# Euro5VDCDC.net
KiCad netlist of a schematic drawn in EAGLE
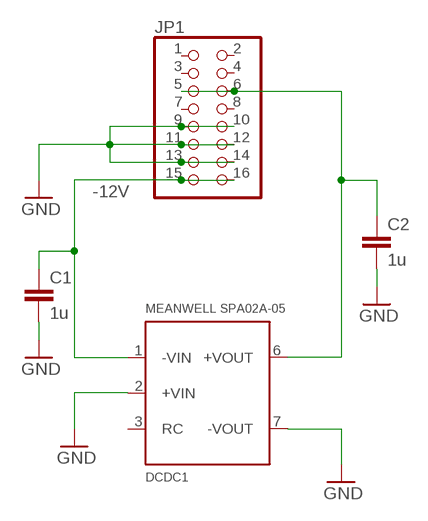
[diagram p0: schematic, sheet 1]

(export (version "E")
  (design (tool "Eeschema 10.0.6"))
  (components
    (comp (ref "C1")
      (value "1u")
      (footprint "eagle-import:C1206K")
      (libsource (lib "eagle-import") (part "C-EUC1206K"))
    )
    (comp (ref "C2")
      (value "1u")
      (footprint "eagle-import:C1206K")
      (libsource (lib "eagle-import") (part "C-EUC1206K"))
    )
    (comp (ref "DCDC1")
      (value "MEANWELL SPA02A-05")
      (footprint "eagle-import:MEANWELL_SPA02")
      (libsource (lib "eagle-import") (part "MEANWELL_SPA02"))
    )
    (comp (ref "JP1")
      (value "PINHD-2X8")
      (footprint "eagle-import:2X08")
      (libsource (lib "eagle-import") (part "PINHD-2X8"))
    )
  )
  (nets
    (net (code "1") (name "/-12V") (class "Default")
      (node (ref "C1") (pin "1") (pinfunction "1_1") (pintype "passive"))
      (node (ref "DCDC1") (pin "1") (pinfunction "-VIN_1") (pintype "bidirectional"))
      (node (ref "JP1") (pin "15") (pinfunction "15_15") (pintype "passive"))
      (node (ref "JP1") (pin "16") (pinfunction "16_16") (pintype "passive"))
    )
    (net (code "2") (name "GND") (class "Default")
      (node (ref "C1") (pin "2") (pinfunction "2_2") (pintype "passive"))
      (node (ref "C2") (pin "2") (pinfunction "2_2") (pintype "passive"))
      (node (ref "DCDC1") (pin "2") (pinfunction "+VIN_2") (pintype "bidirectional"))
      (node (ref "DCDC1") (pin "7") (pinfunction "-VOUT_7") (pintype "bidirectional"))
      (node (ref "JP1") (pin "10") (pinfunction "10_10") (pintype "passive"))
      (node (ref "JP1") (pin "11") (pinfunction "11_11") (pintype "passive"))
      (node (ref "JP1") (pin "12") (pinfunction "12_12") (pintype "passive"))
      (node (ref "JP1") (pin "13") (pinfunction "13_13") (pintype "passive"))
      (node (ref "JP1") (pin "14") (pinfunction "14_14") (pintype "passive"))
      (node (ref "JP1") (pin "9") (pinfunction "9_9") (pintype "passive"))
    )
    (net (code "3") (name "Net-(DCDC1-+VOUT)") (class "Default")
      (node (ref "C2") (pin "1") (pinfunction "1_1") (pintype "passive"))
      (node (ref "DCDC1") (pin "6") (pinfunction "+VOUT_6") (pintype "bidirectional"))
      (node (ref "JP1") (pin "5") (pinfunction "5_5") (pintype "passive"))
      (node (ref "JP1") (pin "6") (pinfunction "6_6") (pintype "passive"))
    )
    (net (code "4") (name "unconnected-(DCDC1-RC-Pad3)") (class "Default")
      (node (ref "DCDC1") (pin "3") (pinfunction "RC_3") (pintype "bidirectional"))
    )
    (net (code "5") (name "unconnected-(JP1-Pad1)") (class "Default")
      (node (ref "JP1") (pin "1") (pinfunction "1_1") (pintype "passive"))
    )
    (net (code "6") (name "unconnected-(JP1-Pad2)") (class "Default")
      (node (ref "JP1") (pin "2") (pinfunction "2_2") (pintype "passive"))
    )
    (net (code "7") (name "unconnected-(JP1-Pad3)") (class "Default")
      (node (ref "JP1") (pin "3") (pinfunction "3_3") (pintype "passive"))
    )
    (net (code "8") (name "unconnected-(JP1-Pad4)") (class "Default")
      (node (ref "JP1") (pin "4") (pinfunction "4_4") (pintype "passive"))
    )
    (net (code "9") (name "unconnected-(JP1-Pad7)") (class "Default")
      (node (ref "JP1") (pin "7") (pinfunction "7_7") (pintype "passive"))
    )
    (net (code "10") (name "unconnected-(JP1-Pad8)") (class "Default")
      (node (ref "JP1") (pin "8") (pinfunction "8_8") (pintype "passive"))
    )
  )
)
